# SCH_Modules.net
KiCad netlist of a schematic drawn in Altium Designer
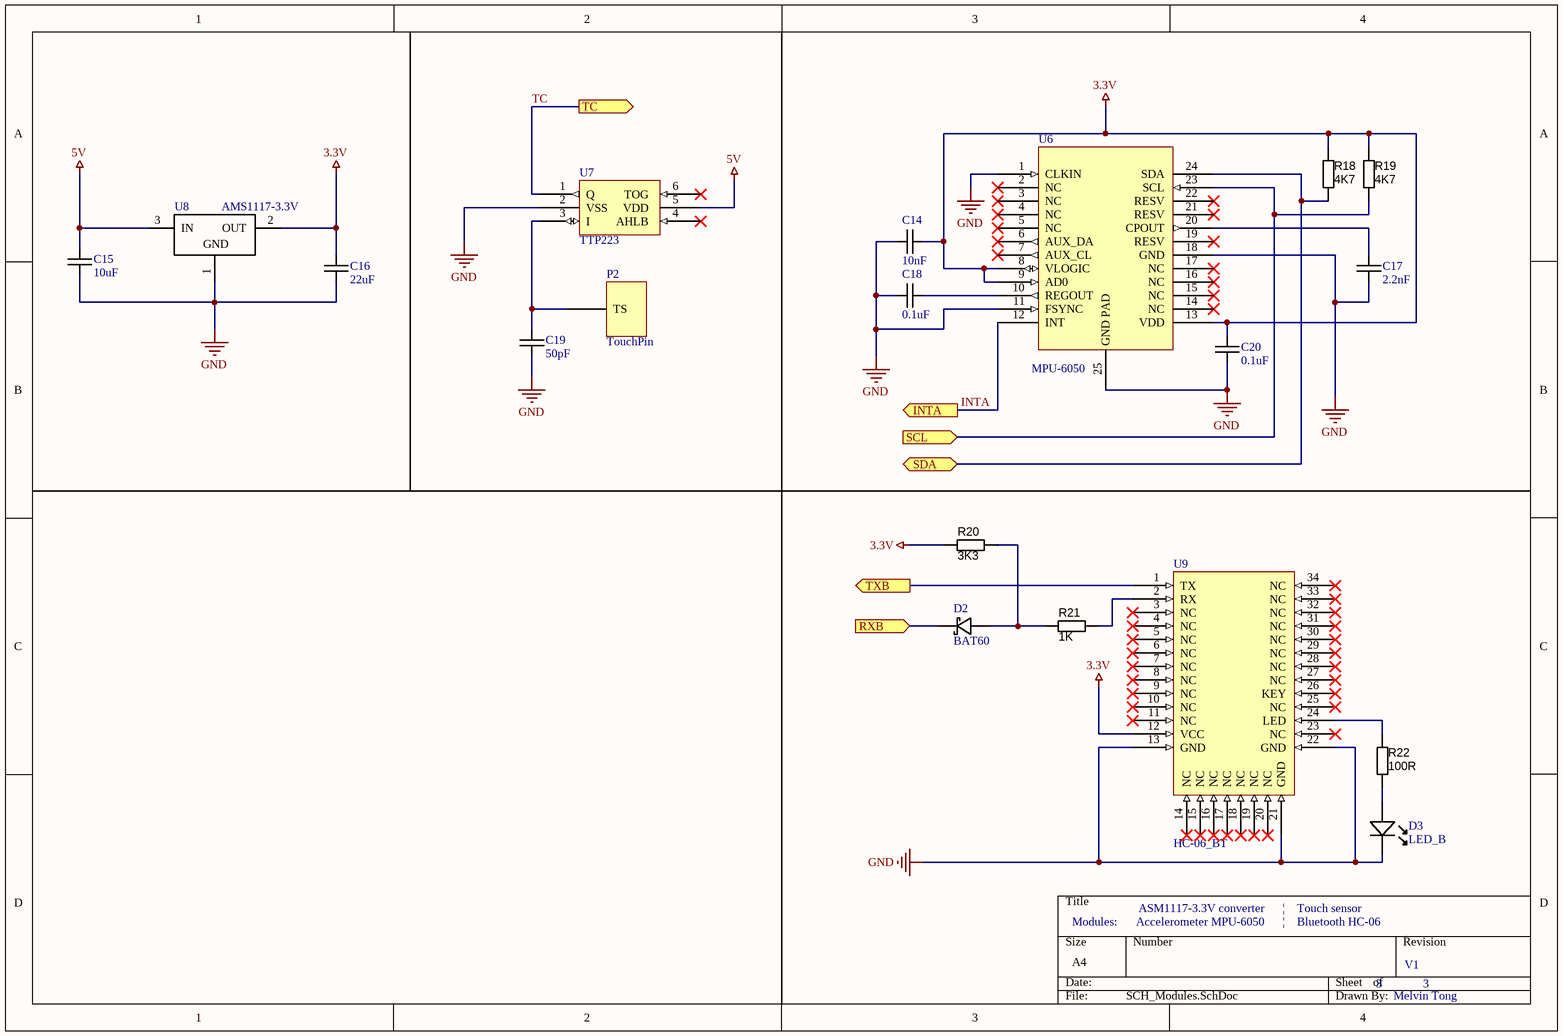
[diagram p0: SCH_Modules.SchDoc]

(export (version "E")
  (design (tool "Eeschema 10.0.6"))
  (components
    (comp (ref "C14")
      (value "10nF")
      (footprint "CAP_0805")
      (description "SMD 0805")
      (libsource (lib "Schlib_Sword") (part "CAP_10nF"))
    )
    (comp (ref "C15")
      (value "10uF")
      (footprint "CAP_1206")
      (description "SMD 0805/1206")
      (libsource (lib "Schlib_Sword") (part "CAP_10uF"))
    )
    (comp (ref "C16")
      (value "22uF")
      (footprint "CAP_1206")
      (description "SMD 1206")
      (libsource (lib "Schlib_Sword") (part "CAP_22uF"))
    )
    (comp (ref "C17")
      (value "2.2nF")
      (footprint "CAP_0805")
      (description "SMD 0805")
      (libsource (lib "Schlib_Sword") (part "CAP_2.2nF"))
    )
    (comp (ref "C18")
      (value "0.1uF")
      (footprint "CAP_0805")
      (description "SMD 0805")
      (libsource (lib "Schlib_Sword") (part "CAP_0.1uF"))
    )
    (comp (ref "C19")
      (value "50pF")
      (footprint "CAP_0805")
      (description "SMD 0805")
      (libsource (lib "Schlib_Sword") (part "CAP_50pF"))
    )
    (comp (ref "C20")
      (value "0.1uF")
      (footprint "CAP_0805")
      (description "SMD 0805")
      (libsource (lib "Schlib_Sword") (part "CAP_0.1uF"))
    )
    (comp (ref "D2")
      (value "BAT60")
      (footprint "SOD323")
      (description "Schottky Diode 3A, Vf~0.24V, Vr=10V")
      (libsource (lib "Schlib_Sword") (part "BAT60"))
    )
    (comp (ref "D3")
      (value "LED_B")
      (footprint "LED_0805")
      (description "SMD_0805 3V")
      (libsource (lib "Schlib_Sword") (part "LED_B"))
    )
    (comp (ref "P2")
      (value "TouchPin")
      (footprint "TouchPad")
      (libsource (lib "Schlib_Sword") (part "TouchPin"))
    )
    (comp (ref "R18")
      (value "4K7")
      (footprint "RESC3216X70N")
      (description "Resistor SMD, 1206")
      (libsource (lib "Schlib_Sword") (part "RES_4K7"))
    )
    (comp (ref "R19")
      (value "4K7")
      (footprint "RESC3216X70N")
      (description "Resistor SMD, 1206")
      (libsource (lib "Schlib_Sword") (part "RES_4K7"))
    )
    (comp (ref "R20")
      (value "3K3")
      (footprint "RESC3216X70N")
      (description "Resistor SMD, 1206")
      (libsource (lib "Schlib_Sword") (part "RES_3K3"))
    )
    (comp (ref "R21")
      (value "1K")
      (footprint "RESC3216X70N")
      (description "Resistor SMD, 1206")
      (libsource (lib "Schlib_Sword") (part "RES_1K"))
    )
    (comp (ref "R22")
      (value "100R")
      (footprint "RESC3216X70N")
      (description "Resistor SMD, 1206")
      (libsource (lib "Schlib_Sword") (part "RES_100R"))
    )
    (comp (ref "U6")
      (value "MPU-6050")
      (footprint "MPU-6050")
      (libsource (lib "Schlib_Sword") (part "MPU-6050"))
    )
    (comp (ref "U7")
      (value "TTP223")
      (footprint "TTP223-BA6")
      (libsource (lib "Schlib_Sword") (part "TTP223"))
    )
    (comp (ref "U8")
      (value "AMS1117-3.3V")
      (footprint "SOT223")
      (libsource (lib "Schlib_Sword") (part "AMS1117-3.3V"))
    )
    (comp (ref "U9")
      (value "HC-06_BT")
      (footprint "HC-06_BT")
      (libsource (lib "Schlib_Sword") (part "HC-06_BT"))
    )
  )
  (nets
    (net (code "1") (name "/INTA") (class "Default")
      (node (ref "U6") (pin "12") (pinfunction "INT_12") (pintype "open_collector"))
    )
    (net (code "2") (name "/RXB") (class "Default")
      (node (ref "D2") (pin "K") (pinfunction "K_K") (pintype "passive"))
    )
    (net (code "3") (name "/SCL") (class "Default")
      (node (ref "R19") (pin "2") (pinfunction "2_2") (pintype "passive"))
      (node (ref "U6") (pin "23") (pinfunction "SCL_23") (pintype "input"))
    )
    (net (code "4") (name "/SDA") (class "Default")
      (node (ref "R18") (pin "2") (pinfunction "2_2") (pintype "passive"))
      (node (ref "U6") (pin "24") (pinfunction "SDA_24") (pintype "open_collector"))
    )
    (net (code "5") (name "/TC") (class "Default")
      (node (ref "U7") (pin "1") (pinfunction "Q_1") (pintype "output"))
    )
    (net (code "6") (name "/TXB") (class "Default")
      (node (ref "U9") (pin "1") (pinfunction "TX_1") (pintype "input"))
    )
    (net (code "7") (name "3.3V") (class "Default")
      (node (ref "C14") (pin "2") (pintype "passive"))
      (node (ref "C16") (pin "1") (pintype "passive"))
      (node (ref "C20") (pin "2") (pintype "passive"))
      (node (ref "R18") (pin "1") (pinfunction "1_1") (pintype "passive"))
      (node (ref "R19") (pin "1") (pinfunction "1_1") (pintype "passive"))
      (node (ref "R20") (pin "1") (pinfunction "1_1") (pintype "passive"))
      (node (ref "U6") (pin "13") (pinfunction "VDD_13") (pintype "power_in"))
      (node (ref "U6") (pin "8") (pinfunction "VLOGIC_8") (pintype "bidirectional"))
      (node (ref "U6") (pin "9") (pinfunction "AD0_9") (pintype "input"))
      (node (ref "U8") (pin "2") (pinfunction "OUT_2") (pintype "power_in"))
      (node (ref "U9") (pin "12") (pinfunction "VCC_12") (pintype "input"))
    )
    (net (code "8") (name "5V") (class "Default")
      (node (ref "C15") (pin "1") (pintype "passive"))
      (node (ref "U7") (pin "5") (pinfunction "VDD_5") (pintype "power_in"))
      (node (ref "U8") (pin "3") (pinfunction "IN_3") (pintype "power_in"))
    )
    (net (code "9") (name "GND") (class "Default")
      (node (ref "C14") (pin "1") (pintype "passive"))
      (node (ref "C15") (pin "2") (pintype "passive"))
      (node (ref "C16") (pin "2") (pintype "passive"))
      (node (ref "C17") (pin "2") (pintype "passive"))
      (node (ref "C18") (pin "1") (pintype "passive"))
      (node (ref "C19") (pin "2") (pintype "passive"))
      (node (ref "C20") (pin "1") (pintype "passive"))
      (node (ref "D3") (pin "K") (pinfunction "K_K") (pintype "passive"))
      (node (ref "U6") (pin "1") (pinfunction "CLKIN_1") (pintype "input"))
      (node (ref "U6") (pin "11") (pinfunction "FSYNC_11") (pintype "input"))
      (node (ref "U6") (pin "18") (pinfunction "GND_18") (pintype "power_in"))
      (node (ref "U6") (pin "25") (pinfunction "GND_PAD_25") (pintype "passive"))
      (node (ref "U7") (pin "2") (pinfunction "VSS_2") (pintype "power_in"))
      (node (ref "U8") (pin "1") (pinfunction "ADJ_1") (pintype "power_in"))
      (node (ref "U9") (pin "13") (pinfunction "GND_13") (pintype "input"))
      (node (ref "U9") (pin "21") (pinfunction "GND_21") (pintype "input"))
      (node (ref "U9") (pin "22") (pinfunction "GND_22") (pintype "input"))
    )
    (net (code "10") (name "Net-(D2-PadA)") (class "Default")
      (node (ref "D2") (pin "A") (pinfunction "A_A") (pintype "passive"))
      (node (ref "R20") (pin "2") (pinfunction "2_2") (pintype "passive"))
      (node (ref "R21") (pin "1") (pinfunction "1_1") (pintype "passive"))
    )
    (net (code "11") (name "Net-(D3-PadA)") (class "Default")
      (node (ref "D3") (pin "A") (pinfunction "A_A") (pintype "passive"))
      (node (ref "R22") (pin "2") (pinfunction "2_2") (pintype "passive"))
    )
    (net (code "12") (name "Net-(P2-TS)") (class "Default")
      (node (ref "C19") (pin "1") (pintype "passive"))
      (node (ref "P2") (pin "1") (pinfunction "TS_1") (pintype "passive"))
      (node (ref "U7") (pin "3") (pinfunction "I_3") (pintype "bidirectional"))
    )
    (net (code "13") (name "Net-(U6-CPOUT)") (class "Default")
      (node (ref "C17") (pin "1") (pintype "passive"))
      (node (ref "U6") (pin "20") (pinfunction "CPOUT_20") (pintype "output"))
    )
    (net (code "14") (name "Net-(U6-REGOUT)") (class "Default")
      (node (ref "C18") (pin "2") (pintype "passive"))
      (node (ref "U6") (pin "10") (pinfunction "REGOUT_10") (pintype "output"))
    )
    (net (code "15") (name "Net-(U9-LED)") (class "Default")
      (node (ref "R22") (pin "1") (pinfunction "1_1") (pintype "passive"))
      (node (ref "U9") (pin "24") (pinfunction "LED_24") (pintype "input"))
    )
    (net (code "16") (name "Net-(U9-RX)") (class "Default")
      (node (ref "R21") (pin "2") (pinfunction "2_2") (pintype "passive"))
      (node (ref "U9") (pin "2") (pinfunction "RX_2") (pintype "input"))
    )
    (net (code "17") (name "unconnected-(U6-AUX_CL-Pad7)") (class "Default")
      (node (ref "U6") (pin "7") (pinfunction "AUX_CL_7") (pintype "output+no_connect"))
    )
    (net (code "18") (name "unconnected-(U6-AUX_DA-Pad6)") (class "Default")
      (node (ref "U6") (pin "6") (pinfunction "AUX_DA_6") (pintype "output+no_connect"))
    )
    (net (code "19") (name "unconnected-(U6-NC-Pad2)") (class "Default")
      (node (ref "U6") (pin "2") (pinfunction "NC_2") (pintype "passive+no_connect"))
    )
    (net (code "20") (name "unconnected-(U6-NC-Pad3)") (class "Default")
      (node (ref "U6") (pin "3") (pinfunction "NC_3") (pintype "passive+no_connect"))
    )
    (net (code "21") (name "unconnected-(U6-NC-Pad4)") (class "Default")
      (node (ref "U6") (pin "4") (pinfunction "NC_4") (pintype "passive+no_connect"))
    )
    (net (code "22") (name "unconnected-(U6-NC-Pad5)") (class "Default")
      (node (ref "U6") (pin "5") (pinfunction "NC_5") (pintype "passive+no_connect"))
    )
    (net (code "23") (name "unconnected-(U6-NC-Pad14)") (class "Default")
      (node (ref "U6") (pin "14") (pinfunction "NC_14") (pintype "passive+no_connect"))
    )
    (net (code "24") (name "unconnected-(U6-NC-Pad15)") (class "Default")
      (node (ref "U6") (pin "15") (pinfunction "NC_15") (pintype "passive+no_connect"))
    )
    (net (code "25") (name "unconnected-(U6-NC-Pad16)") (class "Default")
      (node (ref "U6") (pin "16") (pinfunction "NC_16") (pintype "passive+no_connect"))
    )
    (net (code "26") (name "unconnected-(U6-NC-Pad17)") (class "Default")
      (node (ref "U6") (pin "17") (pinfunction "NC_17") (pintype "passive+no_connect"))
    )
    (net (code "27") (name "unconnected-(U6-RESV-Pad19)") (class "Default")
      (node (ref "U6") (pin "19") (pinfunction "RESV_19") (pintype "passive+no_connect"))
    )
    (net (code "28") (name "unconnected-(U6-RESV-Pad21)") (class "Default")
      (node (ref "U6") (pin "21") (pinfunction "RESV_21") (pintype "passive+no_connect"))
    )
    (net (code "29") (name "unconnected-(U6-RESV-Pad22)") (class "Default")
      (node (ref "U6") (pin "22") (pinfunction "RESV_22") (pintype "passive+no_connect"))
    )
    (net (code "30") (name "unconnected-(U7-AHLB-Pad4)") (class "Default")
      (node (ref "U7") (pin "4") (pinfunction "AHLB_4") (pintype "input+no_connect"))
    )
    (net (code "31") (name "unconnected-(U7-TOG-Pad6)") (class "Default")
      (node (ref "U7") (pin "6") (pinfunction "TOG_6") (pintype "input+no_connect"))
    )
    (net (code "32") (name "unconnected-(U9-KEY-Pad26)") (class "Default")
      (node (ref "U9") (pin "26") (pinfunction "KEY_26") (pintype "input+no_connect"))
    )
    (net (code "33") (name "unconnected-(U9-NC-Pad3)") (class "Default")
      (node (ref "U9") (pin "3") (pinfunction "NC_3") (pintype "input+no_connect"))
    )
    (net (code "34") (name "unconnected-(U9-NC-Pad4)") (class "Default")
      (node (ref "U9") (pin "4") (pinfunction "NC_4") (pintype "input+no_connect"))
    )
    (net (code "35") (name "unconnected-(U9-NC-Pad5)") (class "Default")
      (node (ref "U9") (pin "5") (pinfunction "NC_5") (pintype "input+no_connect"))
    )
    (net (code "36") (name "unconnected-(U9-NC-Pad6)") (class "Default")
      (node (ref "U9") (pin "6") (pinfunction "NC_6") (pintype "input+no_connect"))
    )
    (net (code "37") (name "unconnected-(U9-NC-Pad7)") (class "Default")
      (node (ref "U9") (pin "7") (pinfunction "NC_7") (pintype "input+no_connect"))
    )
    (net (code "38") (name "unconnected-(U9-NC-Pad8)") (class "Default")
      (node (ref "U9") (pin "8") (pinfunction "NC_8") (pintype "input+no_connect"))
    )
    (net (code "39") (name "unconnected-(U9-NC-Pad9)") (class "Default")
      (node (ref "U9") (pin "9") (pinfunction "NC_9") (pintype "input+no_connect"))
    )
    (net (code "40") (name "unconnected-(U9-NC-Pad10)") (class "Default")
      (node (ref "U9") (pin "10") (pinfunction "NC_10") (pintype "input+no_connect"))
    )
    (net (code "41") (name "unconnected-(U9-NC-Pad11)") (class "Default")
      (node (ref "U9") (pin "11") (pinfunction "NC_11") (pintype "input+no_connect"))
    )
    (net (code "42") (name "unconnected-(U9-NC-Pad14)") (class "Default")
      (node (ref "U9") (pin "14") (pinfunction "NC_14") (pintype "input+no_connect"))
    )
    (net (code "43") (name "unconnected-(U9-NC-Pad15)") (class "Default")
      (node (ref "U9") (pin "15") (pinfunction "NC_15") (pintype "input+no_connect"))
    )
    (net (code "44") (name "unconnected-(U9-NC-Pad16)") (class "Default")
      (node (ref "U9") (pin "16") (pinfunction "NC_16") (pintype "input+no_connect"))
    )
    (net (code "45") (name "unconnected-(U9-NC-Pad17)") (class "Default")
      (node (ref "U9") (pin "17") (pinfunction "NC_17") (pintype "input+no_connect"))
    )
    (net (code "46") (name "unconnected-(U9-NC-Pad18)") (class "Default")
      (node (ref "U9") (pin "18") (pinfunction "NC_18") (pintype "input+no_connect"))
    )
    (net (code "47") (name "unconnected-(U9-NC-Pad19)") (class "Default")
      (node (ref "U9") (pin "19") (pinfunction "NC_19") (pintype "input+no_connect"))
    )
    (net (code "48") (name "unconnected-(U9-NC-Pad20)") (class "Default")
      (node (ref "U9") (pin "20") (pinfunction "NC_20") (pintype "input+no_connect"))
    )
    (net (code "49") (name "unconnected-(U9-NC-Pad23)") (class "Default")
      (node (ref "U9") (pin "23") (pinfunction "NC_23") (pintype "input+no_connect"))
    )
    (net (code "50") (name "unconnected-(U9-NC-Pad25)") (class "Default")
      (node (ref "U9") (pin "25") (pinfunction "NC_25") (pintype "input+no_connect"))
    )
    (net (code "51") (name "unconnected-(U9-NC-Pad27)") (class "Default")
      (node (ref "U9") (pin "27") (pinfunction "NC_27") (pintype "input+no_connect"))
    )
    (net (code "52") (name "unconnected-(U9-NC-Pad28)") (class "Default")
      (node (ref "U9") (pin "28") (pinfunction "NC_28") (pintype "input+no_connect"))
    )
    (net (code "53") (name "unconnected-(U9-NC-Pad29)") (class "Default")
      (node (ref "U9") (pin "29") (pinfunction "NC_29") (pintype "input+no_connect"))
    )
    (net (code "54") (name "unconnected-(U9-NC-Pad30)") (class "Default")
      (node (ref "U9") (pin "30") (pinfunction "NC_30") (pintype "input+no_connect"))
    )
    (net (code "55") (name "unconnected-(U9-NC-Pad31)") (class "Default")
      (node (ref "U9") (pin "31") (pinfunction "NC_31") (pintype "input+no_connect"))
    )
    (net (code "56") (name "unconnected-(U9-NC-Pad32)") (class "Default")
      (node (ref "U9") (pin "32") (pinfunction "NC_32") (pintype "input+no_connect"))
    )
    (net (code "57") (name "unconnected-(U9-NC-Pad33)") (class "Default")
      (node (ref "U9") (pin "33") (pinfunction "NC_33") (pintype "input+no_connect"))
    )
    (net (code "58") (name "unconnected-(U9-NC-Pad34)") (class "Default")
      (node (ref "U9") (pin "34") (pinfunction "NC_34") (pintype "input+no_connect"))
    )
  )
)
